# skull_white.net
KiCad netlist of a schematic drawn in EAGLE
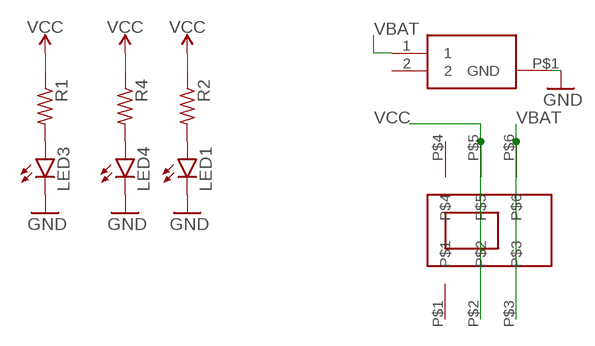
[diagram p0: schematic, sheet 1]

(export (version "E")
  (design (tool "Eeschema 10.0.6"))
  (components
    (comp (ref "LED1")
      (value "LEDCHIP-LED0805")
      (footprint "eagle-import:CHIP-LED0805")
      (libsource (lib "eagle-import") (part "LEDCHIP-LED0805"))
    )
    (comp (ref "LED3")
      (value "LEDCHIP-LED0805")
      (footprint "eagle-import:CHIP-LED0805")
      (libsource (lib "eagle-import") (part "LEDCHIP-LED0805"))
    )
    (comp (ref "LED4")
      (value "LEDCHIP-LED0805")
      (footprint "eagle-import:CHIP-LED0805")
      (libsource (lib "eagle-import") (part "LEDCHIP-LED0805"))
    )
    (comp (ref "R1")
      (value "R-US_R0603")
      (footprint "eagle-import:R0603")
      (libsource (lib "eagle-import") (part "R-US_R0603"))
    )
    (comp (ref "R2")
      (value "R-US_R0603")
      (footprint "eagle-import:R0603")
      (libsource (lib "eagle-import") (part "R-US_R0603"))
    )
    (comp (ref "R4")
      (value "R-US_R0603")
      (footprint "eagle-import:R0603")
      (libsource (lib "eagle-import") (part "R-US_R0603"))
    )
    (comp (ref "U$1")
      (value "CL-SB-22A-02T-SLIDE-SWITCH-TUCKED-PADS")
      (footprint "eagle-import:CL-SB-22A-02T-DPDT-COMPACT-SWITCH")
      (libsource (lib "eagle-import") (part "CL-SB-22A-02T-SLIDE-SWITCH-TUCKED-PADS"))
    )
    (comp (ref "VBAT")
      (value "BAT-HLD-012-SMT")
      (footprint "eagle-import:BATHLD012SMT")
      (fields (field (name "MOUSER_PART_NUMBER") "712-BAT-HLD-012-SMT"))
      (libsource (lib "eagle-import") (part "BAT-HLD-012-SMT"))
    )
  )
  (nets
    (net (code "1") (name "/VBAT") (class "Default")
      (node (ref "U$1") (pin "P$3") (pinfunction "P$3_P$3") (pintype "bidirectional"))
      (node (ref "U$1") (pin "P$6") (pinfunction "P$6_P$6") (pintype "bidirectional"))
      (node (ref "VBAT") (pin "1") (pinfunction "1_1") (pintype "bidirectional"))
    )
    (net (code "2") (name "GND") (class "Default")
      (node (ref "LED1") (pin "C") (pinfunction "C_C") (pintype "passive"))
      (node (ref "LED3") (pin "C") (pinfunction "C_C") (pintype "passive"))
      (node (ref "LED4") (pin "C") (pinfunction "C_C") (pintype "passive"))
      (node (ref "VBAT") (pin "P$1") (pinfunction "GND_P$1") (pintype "bidirectional"))
    )
    (net (code "3") (name "Net-(LED1-PadA)") (class "Default")
      (node (ref "LED1") (pin "A") (pinfunction "A_A") (pintype "passive"))
      (node (ref "R2") (pin "2") (pinfunction "2_2") (pintype "passive"))
    )
    (net (code "4") (name "Net-(LED3-PadA)") (class "Default")
      (node (ref "LED3") (pin "A") (pinfunction "A_A") (pintype "passive"))
      (node (ref "R1") (pin "2") (pinfunction "2_2") (pintype "passive"))
    )
    (net (code "5") (name "Net-(LED4-PadA)") (class "Default")
      (node (ref "LED4") (pin "A") (pinfunction "A_A") (pintype "passive"))
      (node (ref "R4") (pin "2") (pinfunction "2_2") (pintype "passive"))
    )
    (net (code "6") (name "VCC") (class "Default")
      (node (ref "R1") (pin "1") (pinfunction "1_1") (pintype "passive"))
      (node (ref "R2") (pin "1") (pinfunction "1_1") (pintype "passive"))
      (node (ref "R4") (pin "1") (pinfunction "1_1") (pintype "passive"))
      (node (ref "U$1") (pin "P$2") (pinfunction "P$2_P$2") (pintype "bidirectional"))
      (node (ref "U$1") (pin "P$5") (pinfunction "P$5_P$5") (pintype "bidirectional"))
    )
    (net (code "7") (name "unconnected-(U$1-PadP$1)") (class "Default")
      (node (ref "U$1") (pin "P$1") (pinfunction "P$1_P$1") (pintype "bidirectional"))
    )
    (net (code "8") (name "unconnected-(U$1-PadP$4)") (class "Default")
      (node (ref "U$1") (pin "P$4") (pinfunction "P$4_P$4") (pintype "bidirectional"))
    )
    (net (code "9") (name "unconnected-(VBAT-Pad2)") (class "Default")
      (node (ref "VBAT") (pin "2") (pinfunction "2_2") (pintype "bidirectional"))
    )
  )
)
